# HoloProjector_LED_I2C_v1_0.net
KiCad netlist of a schematic drawn in EAGLE
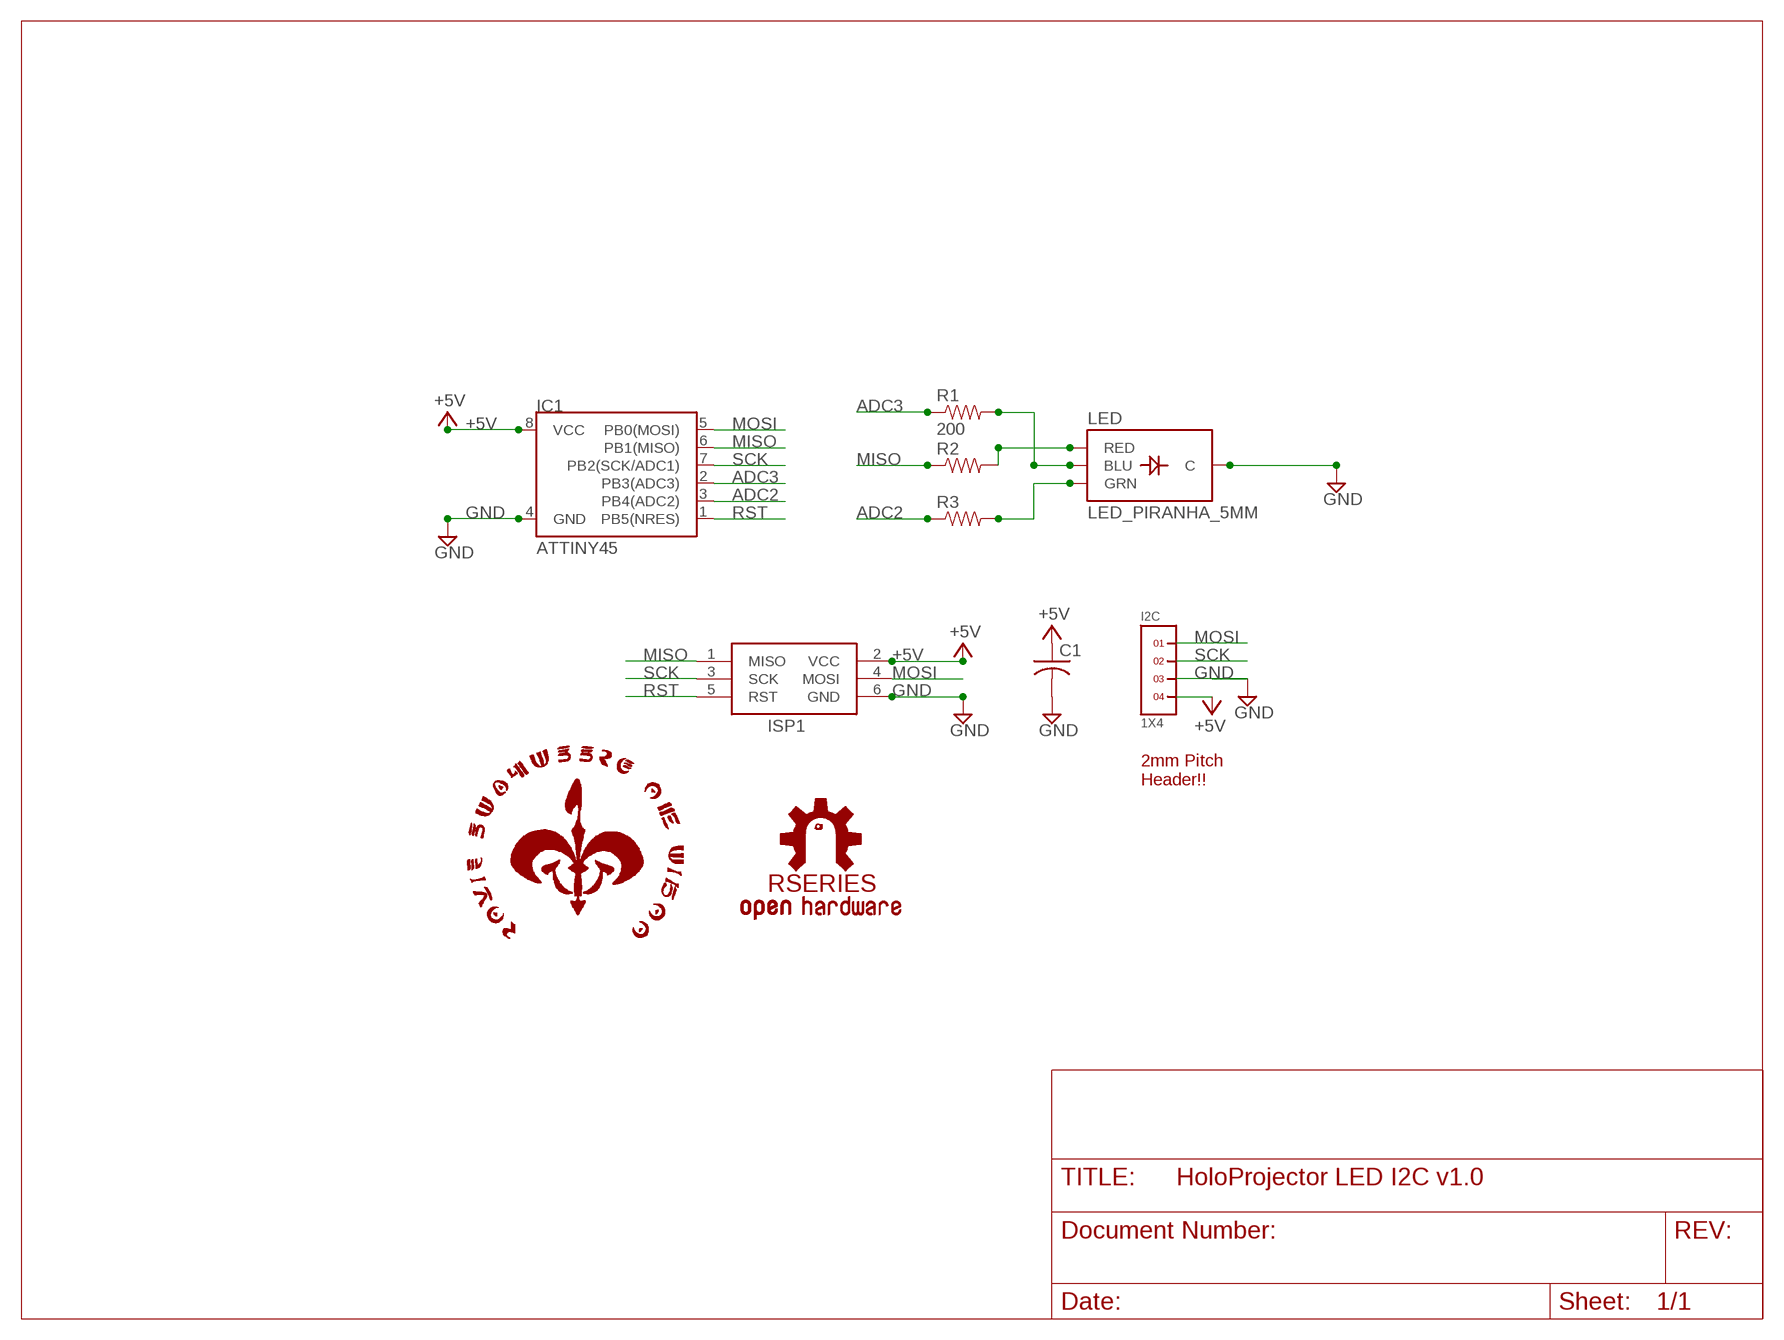
[diagram p0: schematic, sheet 1]

(export (version "E")
  (design (tool "Eeschema 10.0.6"))
  (components
    (comp (ref "C1")
      (value "C-USC1206K")
      (footprint "eagle-import:C1206K")
      (libsource (lib "eagle-import") (part "C-USC1206K"))
    )
    (comp (ref "I2C")
      (value "1X4")
      (footprint "eagle-import:1X4")
      (libsource (lib "eagle-import") (part "1X4"))
    )
    (comp (ref "IC1")
      (value "ATTINY45")
      (footprint "eagle-import:SO08-EIAJ")
      (libsource (lib "eagle-import") (part "ATTINY45"))
    )
    (comp (ref "ISP1")
      (value "AVRISP-6")
      (footprint "eagle-import:AVRISP")
      (libsource (lib "eagle-import") (part "AVRISP-6"))
    )
    (comp (ref "LED")
      (value "LED_PIRANHA_5MM")
      (footprint "eagle-import:LED_PIRANHA_5MM")
      (libsource (lib "eagle-import") (part "LED_PIRANHA_5MM"))
    )
    (comp (ref "R1")
      (value "200")
      (footprint "eagle-import:1206")
      (libsource (lib "eagle-import") (part "RESISTOR1206"))
    )
    (comp (ref "R2")
      (value "RESISTOR1206")
      (footprint "eagle-import:1206")
      (libsource (lib "eagle-import") (part "RESISTOR1206"))
    )
    (comp (ref "R3")
      (value "RESISTOR1206")
      (footprint "eagle-import:1206")
      (libsource (lib "eagle-import") (part "RESISTOR1206"))
    )
    (comp (ref "U$1")
      (value "ROYAL-ENGINEERS-OF-NABOOSMALL")
      (footprint "eagle-import:ROYAL-ENGINEERS-OF-NABOO-SMALL")
      (libsource (lib "eagle-import") (part "ROYAL-ENGINEERS-OF-NABOOSMALL"))
    )
    (comp (ref "U$2")
      (value "RSERIES-OSHW-LOGOMEDIUM")
      (footprint "eagle-import:RSERIES-OSHW-LOGO-MEDIUM")
      (libsource (lib "eagle-import") (part "RSERIES-OSHW-LOGOMEDIUM"))
    )
  )
  (nets
    (net (code "1") (name "+5V") (class "Default")
      (node (ref "C1") (pin "1") (pinfunction "1_1") (pintype "passive"))
      (node (ref "I2C") (pin "4") (pinfunction "4_4") (pintype "bidirectional"))
      (node (ref "IC1") (pin "8") (pinfunction "VCC_8") (pintype "bidirectional"))
      (node (ref "ISP1") (pin "2") (pinfunction "VCC_2") (pintype "power_in"))
    )
    (net (code "2") (name "/ADC2") (class "Default")
      (node (ref "IC1") (pin "3") (pinfunction "PB4(ADC2)_3") (pintype "bidirectional"))
      (node (ref "R3") (pin "1") (pinfunction "1_1") (pintype "passive"))
    )
    (net (code "3") (name "/ADC3") (class "Default")
      (node (ref "IC1") (pin "2") (pinfunction "PB3(ADC3)_2") (pintype "bidirectional"))
      (node (ref "R1") (pin "1") (pinfunction "1_1") (pintype "passive"))
    )
    (net (code "4") (name "/MISO") (class "Default")
      (node (ref "IC1") (pin "6") (pinfunction "PB1(MISO)_6") (pintype "bidirectional"))
      (node (ref "ISP1") (pin "1") (pinfunction "MISO_1") (pintype "input"))
      (node (ref "R2") (pin "1") (pinfunction "1_1") (pintype "passive"))
    )
    (net (code "5") (name "/MOSI") (class "Default")
      (node (ref "I2C") (pin "1") (pinfunction "1_1") (pintype "bidirectional"))
      (node (ref "IC1") (pin "5") (pinfunction "PB0(MOSI)_5") (pintype "bidirectional"))
      (node (ref "ISP1") (pin "4") (pinfunction "MOSI_4") (pintype "output"))
    )
    (net (code "6") (name "/RST") (class "Default")
      (node (ref "IC1") (pin "1") (pinfunction "PB5(NRES)_1") (pintype "bidirectional"))
      (node (ref "ISP1") (pin "5") (pinfunction "RST_5") (pintype "output"))
    )
    (net (code "7") (name "/SCK") (class "Default")
      (node (ref "I2C") (pin "2") (pinfunction "2_2") (pintype "bidirectional"))
      (node (ref "IC1") (pin "7") (pinfunction "PB2(SCK/ADC1)_7") (pintype "bidirectional"))
      (node (ref "ISP1") (pin "3") (pinfunction "SCK_3") (pintype "output"))
    )
    (net (code "8") (name "GND") (class "Default")
      (node (ref "C1") (pin "2") (pinfunction "2_2") (pintype "passive"))
      (node (ref "I2C") (pin "3") (pinfunction "3_3") (pintype "bidirectional"))
      (node (ref "IC1") (pin "4") (pinfunction "GND_4") (pintype "bidirectional"))
      (node (ref "ISP1") (pin "6") (pinfunction "GND_6") (pintype "power_in"))
      (node (ref "LED") (pin "-") (pinfunction "C_-") (pintype "bidirectional"))
    )
    (net (code "9") (name "Net-(LED-BLU)") (class "Default")
      (node (ref "LED") (pin "B") (pinfunction "BLU_B") (pintype "bidirectional"))
      (node (ref "R1") (pin "2") (pinfunction "2_2") (pintype "passive"))
    )
    (net (code "10") (name "Net-(LED-GRN)") (class "Default")
      (node (ref "LED") (pin "G") (pinfunction "GRN_G") (pintype "bidirectional"))
      (node (ref "R3") (pin "2") (pinfunction "2_2") (pintype "passive"))
    )
    (net (code "11") (name "Net-(LED-RED)") (class "Default")
      (node (ref "LED") (pin "R") (pinfunction "RED_R") (pintype "bidirectional"))
      (node (ref "R2") (pin "2") (pinfunction "2_2") (pintype "passive"))
    )
  )
)
